# AjusteVoltajeRX.net
KiCad netlist of a schematic drawn in Altium Designer
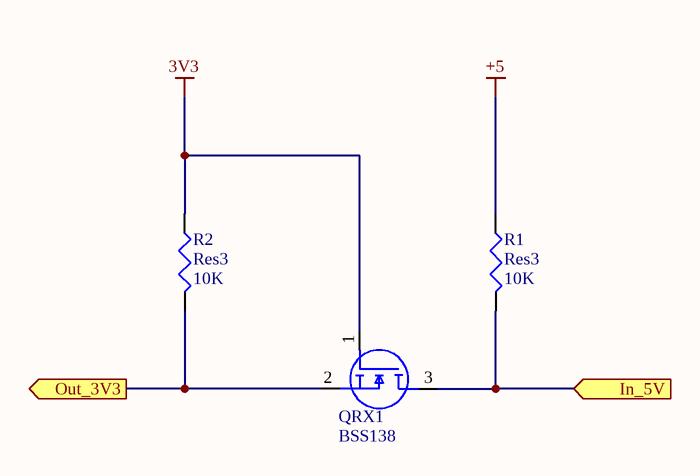
[diagram p0: AjusteVoltajeRX.SchDoc]

(export (version "E")
  (design (tool "Eeschema 10.0.6"))
  (components
    (comp (ref "QRX1")
      (value "BSS138")
      (footprint "ComponentesLayOut:SOT95P240X120-3N")
      (description "MOSFET (N-Channel)")
      (fields (field (name "MOUSER PART NUMBER") "512-BSS138"))
      (libsource (lib "CompontentesEsquemáticos") (part "BSS138"))
    )
    (comp (ref "R1")
      (value "Res3")
      (footprint "J1-0603")
      (description "Resistor")
      (fields (field (name "ALTIUM_VALUE") "10K") (field (name "PUBLISHER") "Altium Limited"))
      (libsource (lib "Miscellaneous Devices") (part "Res3"))
    )
    (comp (ref "R2")
      (value "Res3")
      (footprint "J1-0603")
      (description "Resistor")
      (fields (field (name "ALTIUM_VALUE") "10K") (field (name "PUBLISHER") "Altium Limited"))
      (libsource (lib "Miscellaneous Devices") (part "Res3"))
    )
  )
  (nets
    (net (code "1") (name "+5") (class "Default")
      (node (ref "R1") (pin "1") (pinfunction "1_1") (pintype "passive"))
    )
    (net (code "2") (name "/In_5V") (class "Default")
      (node (ref "QRX1") (pin "3") (pinfunction "D_3") (pintype "passive"))
      (node (ref "R1") (pin "2") (pinfunction "2_2") (pintype "passive"))
    )
    (net (code "3") (name "/Out_3V3") (class "Default")
      (node (ref "QRX1") (pin "2") (pinfunction "S_2") (pintype "passive"))
      (node (ref "R2") (pin "2") (pinfunction "2_2") (pintype "passive"))
    )
    (net (code "4") (name "3V3") (class "Default")
      (node (ref "QRX1") (pin "1") (pinfunction "G_1") (pintype "passive"))
      (node (ref "R2") (pin "1") (pinfunction "1_1") (pintype "passive"))
    )
  )
)
